# thermometre-v3-powersupply.net
KiCad netlist of a schematic drawn in EAGLE
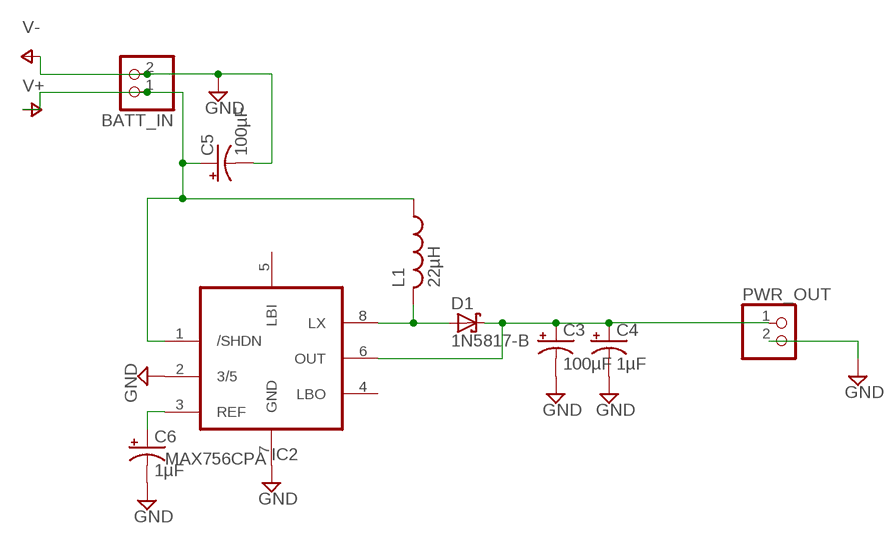
[diagram p0: schematic, sheet 1]

(export (version "E")
  (design (tool "Eeschema 10.0.6"))
  (components
    (comp (ref "BATT_IN")
      (value "PINHD-1X2")
      (footprint "eagle-import:1X02")
      (libsource (lib "eagle-import") (part "PINHD-1X2"))
    )
    (comp (ref "C3")
      (value "100µF")
      (footprint "eagle-import:E2-5")
      (libsource (lib "eagle-import") (part "CPOL-USE2-5"))
    )
    (comp (ref "C4")
      (value "1µF")
      (footprint "eagle-import:E2-5")
      (libsource (lib "eagle-import") (part "CPOL-USE2-5"))
    )
    (comp (ref "C5")
      (value "100µF")
      (footprint "eagle-import:E2,5-5")
      (libsource (lib "eagle-import") (part "rcl_CPOL-USE2.5-5"))
    )
    (comp (ref "C6")
      (value "1µF")
      (footprint "eagle-import:E2,5-5")
      (libsource (lib "eagle-import") (part "rcl_CPOL-USE2.5-5"))
    )
    (comp (ref "D1")
      (value "1N5817-B")
      (footprint "eagle-import:DO41-7.6")
      (libsource (lib "eagle-import") (part "1N5817-B"))
    )
    (comp (ref "IC2")
      (value "MAX756CPA")
      (footprint "eagle-import:DIL08")
      (libsource (lib "eagle-import") (part "MAX756CPA"))
    )
    (comp (ref "L1")
      (value "22µH")
      (footprint "eagle-import:0204_7")
      (libsource (lib "eagle-import") (part "L-US0204/7"))
    )
    (comp (ref "PWR_OUT")
      (value "PINHD-1X2")
      (footprint "eagle-import:1X02")
      (libsource (lib "eagle-import") (part "PINHD-1X2"))
    )
  )
  (nets
    (net (code "1") (name "GND") (class "Default")
      (node (ref "BATT_IN") (pin "2") (pinfunction "2_2") (pintype "passive"))
      (node (ref "C3") (pin "-") (pinfunction "-_-") (pintype "passive"))
      (node (ref "C4") (pin "-") (pinfunction "-_-") (pintype "passive"))
      (node (ref "C5") (pin "-") (pinfunction "-_-") (pintype "passive"))
      (node (ref "C6") (pin "-") (pinfunction "-_-") (pintype "passive"))
      (node (ref "IC2") (pin "2") (pinfunction "3/5_2") (pintype "bidirectional"))
      (node (ref "IC2") (pin "7") (pinfunction "GND_7") (pintype "power_in"))
      (node (ref "PWR_OUT") (pin "2") (pinfunction "2_2") (pintype "passive"))
    )
    (net (code "2") (name "Net-(IC2-LX)") (class "Default")
      (node (ref "D1") (pin "A") (pinfunction "A_A") (pintype "passive"))
      (node (ref "IC2") (pin "8") (pinfunction "LX_8") (pintype "output"))
      (node (ref "L1") (pin "2") (pinfunction "2_2") (pintype "passive"))
    )
    (net (code "3") (name "Net-(IC2-OUT)") (class "Default")
      (node (ref "C3") (pin "+") (pinfunction "+_+") (pintype "passive"))
      (node (ref "C4") (pin "+") (pinfunction "+_+") (pintype "passive"))
      (node (ref "D1") (pin "C") (pinfunction "C_C") (pintype "passive"))
      (node (ref "IC2") (pin "6") (pinfunction "OUT_6") (pintype "output"))
      (node (ref "PWR_OUT") (pin "1") (pinfunction "1_1") (pintype "passive"))
    )
    (net (code "4") (name "Net-(IC2-REF)") (class "Default")
      (node (ref "C6") (pin "+") (pinfunction "+_+") (pintype "passive"))
      (node (ref "IC2") (pin "3") (pinfunction "REF_3") (pintype "passive"))
    )
    (net (code "5") (name "V+") (class "Default")
      (node (ref "BATT_IN") (pin "1") (pinfunction "1_1") (pintype "passive"))
      (node (ref "C5") (pin "+") (pinfunction "+_+") (pintype "passive"))
      (node (ref "IC2") (pin "1") (pinfunction "/SHDN_1") (pintype "input"))
      (node (ref "L1") (pin "1") (pinfunction "1_1") (pintype "passive"))
    )
    (net (code "6") (name "unconnected-(IC2-LBI-Pad5)") (class "Default")
      (node (ref "IC2") (pin "5") (pinfunction "LBI_5") (pintype "input"))
    )
    (net (code "7") (name "unconnected-(IC2-LBO-Pad4)") (class "Default")
      (node (ref "IC2") (pin "4") (pinfunction "LBO_4") (pintype "input"))
    )
  )
)
